# 2_ADSTM32-MCU.net
KiCad netlist of a schematic drawn in Altium Designer
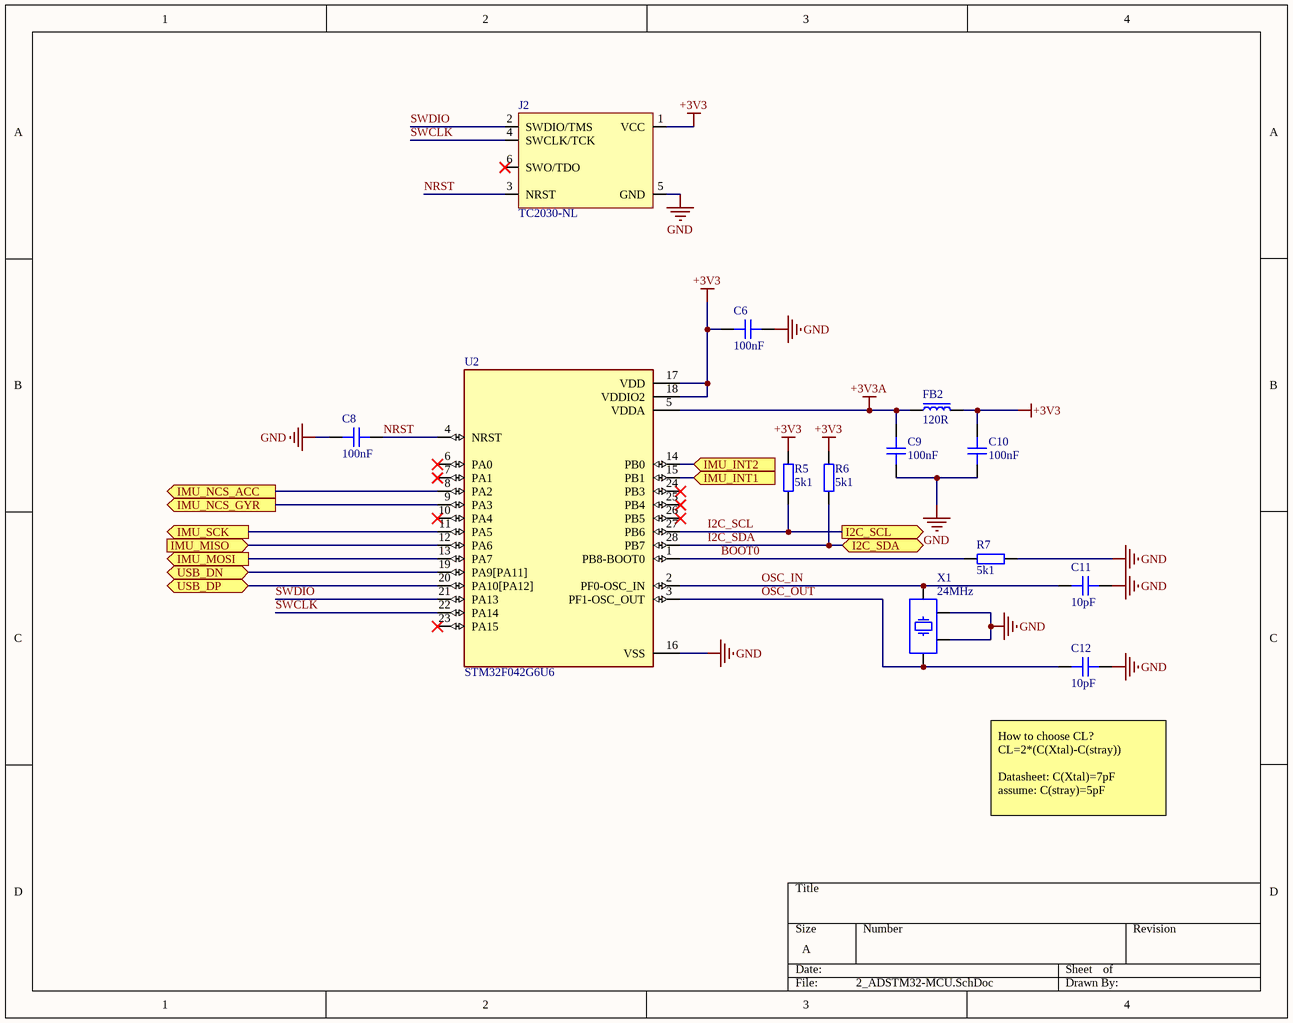
[diagram p0: 2_ADSTM32-MCU.SchDoc]

(export (version "E")
  (design (tool "Eeschema 10.0.6"))
  (components
    (comp (ref "C6")
      (value "100nF")
      (footprint "CAP_0603")
      (description "Capacitor SMD 0603")
      (libsource (lib "Schematic-Lib-PhilsLab") (part "CAP_0603"))
    )
    (comp (ref "C8")
      (value "100nF")
      (footprint "CAP_0603")
      (description "Capacitor SMD 0603")
      (libsource (lib "Schematic-Lib-PhilsLab") (part "CAP_0603"))
    )
    (comp (ref "C9")
      (value "100nF")
      (footprint "CAP_0603")
      (description "Capacitor SMD 0603")
      (libsource (lib "Schematic-Lib-PhilsLab") (part "CAP_0603"))
    )
    (comp (ref "C10")
      (value "100nF")
      (footprint "CAP_0603")
      (description "Capacitor SMD 0603")
      (libsource (lib "Schematic-Lib-PhilsLab") (part "CAP_0603"))
    )
    (comp (ref "C11")
      (value "10pF")
      (footprint "CAP_0603")
      (description "Capacitor SMD 0603")
      (libsource (lib "Schematic-Lib-PhilsLab") (part "CAP_0603"))
    )
    (comp (ref "C12")
      (value "10pF")
      (footprint "CAP_0603")
      (description "Capacitor SMD 0603")
      (libsource (lib "Schematic-Lib-PhilsLab") (part "CAP_0603"))
    )
    (comp (ref "FB2")
      (value "120R")
      (footprint "FB_0603")
      (description "Ferrite Bead SMD 0603")
      (libsource (lib "Schematic-Lib-PhilsLab") (part "FB_0603"))
    )
    (comp (ref "J2")
      (value "TC2030-NL")
      (footprint "TC2030-NL-FP")
      (description "Tag-Connect No-Solder SWD Debug Connector (No Legs) DO NOT PLACE")
      (fields
        (field (name "MANUFACTURER") "Tag-Connect")
        (field (name "MANUFACTURER PART NUMBER") "TC2030-NL-FP")
      )
      (libsource (lib "Schematic-Lib-PhilsLab") (part "TC2030-NL"))
    )
    (comp (ref "R5")
      (value "5k1")
      (footprint "RES_0603")
      (description "Resistor SMD 0603")
      (libsource (lib "Schematic-Lib-PhilsLab") (part "RES_0603"))
    )
    (comp (ref "R6")
      (value "5k1")
      (footprint "RES_0603")
      (description "Resistor SMD 0603")
      (libsource (lib "Schematic-Lib-PhilsLab") (part "RES_0603"))
    )
    (comp (ref "R7")
      (value "5k1")
      (footprint "RES_0603")
      (description "Resistor SMD 0603")
      (libsource (lib "Schematic-Lib-PhilsLab") (part "RES_0603"))
    )
    (comp (ref "U2")
      (value "STM32F042G6U6")
      (footprint "STM32F042G6U6")
      (fields (field (name "MANUFACTURER") "STMicroelectronics"))
      (libsource (lib "Schlib1") (part "STM32F042G6U6"))
    )
    (comp (ref "X1")
      (value "24MHz")
      (footprint "XTAL_3225")
      (description "Crystal SMD 24MHz 10PPM 7pF 3225")
      (fields
        (field (name "MANUFACTURER") "Epson")
        (field (name "MANUFACTURER PART NUMBER") "TSX-3225 24.0000MF15X-AC")
      )
      (libsource (lib "Schematic-Lib-PhilsLab") (part "TSX-3225_24.0000MF15X-AC"))
    )
  )
  (nets
    (net (code "1") (name "+3V3") (class "Default")
      (node (ref "C10") (pin "2") (pinfunction "2_2") (pintype "passive"))
      (node (ref "C6") (pin "2") (pinfunction "2_2") (pintype "passive"))
      (node (ref "FB2") (pin "2") (pinfunction "2_2") (pintype "passive"))
      (node (ref "J2") (pin "1") (pinfunction "VCC_1") (pintype "passive"))
      (node (ref "R5") (pin "2") (pinfunction "2_2") (pintype "passive"))
      (node (ref "R6") (pin "2") (pinfunction "2_2") (pintype "passive"))
      (node (ref "U2") (pin "17") (pinfunction "VDD_17") (pintype "power_in"))
      (node (ref "U2") (pin "18") (pinfunction "VDDIO2_18") (pintype "power_in"))
    )
    (net (code "2") (name "+3V3A") (class "Default")
      (node (ref "C9") (pin "2") (pinfunction "2_2") (pintype "passive"))
      (node (ref "FB2") (pin "1") (pinfunction "1_1") (pintype "passive"))
      (node (ref "U2") (pin "5") (pinfunction "VDDA_5") (pintype "power_in"))
    )
    (net (code "3") (name "/BOOT0") (class "Default")
      (node (ref "R7") (pin "2") (pinfunction "2_2") (pintype "passive"))
      (node (ref "U2") (pin "1") (pinfunction "PB8-BOOT0_1") (pintype "bidirectional"))
    )
    (net (code "4") (name "/I2C_SCL") (class "Default")
      (node (ref "R5") (pin "1") (pinfunction "1_1") (pintype "passive"))
      (node (ref "U2") (pin "27") (pinfunction "PB6_27") (pintype "bidirectional"))
    )
    (net (code "5") (name "/I2C_SDA") (class "Default")
      (node (ref "R6") (pin "1") (pinfunction "1_1") (pintype "passive"))
      (node (ref "U2") (pin "28") (pinfunction "PB7_28") (pintype "bidirectional"))
    )
    (net (code "6") (name "/IMU_INT1") (class "Default")
      (node (ref "U2") (pin "15") (pinfunction "PB1_15") (pintype "bidirectional"))
    )
    (net (code "7") (name "/IMU_INT2") (class "Default")
      (node (ref "U2") (pin "14") (pinfunction "PB0_14") (pintype "bidirectional"))
    )
    (net (code "8") (name "/IMU_MISO") (class "Default")
      (node (ref "U2") (pin "12") (pinfunction "PA6_12") (pintype "bidirectional"))
    )
    (net (code "9") (name "/IMU_MOSI") (class "Default")
      (node (ref "U2") (pin "13") (pinfunction "PA7_13") (pintype "bidirectional"))
    )
    (net (code "10") (name "/IMU_NCS_ACC") (class "Default")
      (node (ref "U2") (pin "8") (pinfunction "PA2_8") (pintype "bidirectional"))
    )
    (net (code "11") (name "/IMU_NCS_GYR") (class "Default")
      (node (ref "U2") (pin "9") (pinfunction "PA3_9") (pintype "bidirectional"))
    )
    (net (code "12") (name "/IMU_SCK") (class "Default")
      (node (ref "U2") (pin "11") (pinfunction "PA5_11") (pintype "bidirectional"))
    )
    (net (code "13") (name "/NRST") (class "Default")
      (node (ref "C8") (pin "1") (pinfunction "1_1") (pintype "passive"))
      (node (ref "J2") (pin "3") (pinfunction "NRST_3") (pintype "passive"))
      (node (ref "U2") (pin "4") (pinfunction "NRST_4") (pintype "bidirectional"))
    )
    (net (code "14") (name "/OSC_IN") (class "Default")
      (node (ref "C11") (pin "2") (pinfunction "2_2") (pintype "passive"))
      (node (ref "U2") (pin "2") (pinfunction "PF0-OSC_IN_2") (pintype "bidirectional"))
      (node (ref "X1") (pin "3") (pinfunction "3_3") (pintype "passive"))
    )
    (net (code "15") (name "/OSC_OUT") (class "Default")
      (node (ref "C12") (pin "2") (pinfunction "2_2") (pintype "passive"))
      (node (ref "U2") (pin "3") (pinfunction "PF1-OSC_OUT_3") (pintype "bidirectional"))
      (node (ref "X1") (pin "1") (pinfunction "1_1") (pintype "passive"))
    )
    (net (code "16") (name "/SWCLK") (class "Default")
      (node (ref "J2") (pin "4") (pinfunction "SWCLK/TCK_4") (pintype "passive"))
      (node (ref "U2") (pin "22") (pinfunction "PA14_22") (pintype "bidirectional"))
    )
    (net (code "17") (name "/SWDIO") (class "Default")
      (node (ref "J2") (pin "2") (pinfunction "SWDIO/TMS_2") (pintype "passive"))
      (node (ref "U2") (pin "21") (pinfunction "PA13_21") (pintype "bidirectional"))
    )
    (net (code "18") (name "/USB_DN") (class "Default")
      (node (ref "U2") (pin "19") (pinfunction "PA9[PA11]_19") (pintype "bidirectional"))
    )
    (net (code "19") (name "/USB_DP") (class "Default")
      (node (ref "U2") (pin "20") (pinfunction "PA10[PA12]_20") (pintype "bidirectional"))
    )
    (net (code "20") (name "GND") (class "Default")
      (node (ref "C10") (pin "1") (pinfunction "1_1") (pintype "passive"))
      (node (ref "C11") (pin "1") (pinfunction "1_1") (pintype "passive"))
      (node (ref "C12") (pin "1") (pinfunction "1_1") (pintype "passive"))
      (node (ref "C6") (pin "1") (pinfunction "1_1") (pintype "passive"))
      (node (ref "C8") (pin "2") (pinfunction "2_2") (pintype "passive"))
      (node (ref "C9") (pin "1") (pinfunction "1_1") (pintype "passive"))
      (node (ref "J2") (pin "5") (pinfunction "GND_5") (pintype "passive"))
      (node (ref "R7") (pin "1") (pinfunction "1_1") (pintype "passive"))
      (node (ref "U2") (pin "16") (pinfunction "VSS_16") (pintype "power_in"))
      (node (ref "X1") (pin "2") (pinfunction "2_2") (pintype "passive"))
      (node (ref "X1") (pin "4") (pinfunction "4_4") (pintype "passive"))
    )
    (net (code "21") (name "unconnected-(J2-SWO{slash}TDO-Pad6)") (class "Default")
      (node (ref "J2") (pin "6") (pinfunction "SWO/TDO_6") (pintype "passive+no_connect"))
    )
    (net (code "22") (name "unconnected-(U2-PA0-Pad6)") (class "Default")
      (node (ref "U2") (pin "6") (pinfunction "PA0_6") (pintype "bidirectional+no_connect"))
    )
    (net (code "23") (name "unconnected-(U2-PA1-Pad7)") (class "Default")
      (node (ref "U2") (pin "7") (pinfunction "PA1_7") (pintype "bidirectional+no_connect"))
    )
    (net (code "24") (name "unconnected-(U2-PA4-Pad10)") (class "Default")
      (node (ref "U2") (pin "10") (pinfunction "PA4_10") (pintype "bidirectional+no_connect"))
    )
    (net (code "25") (name "unconnected-(U2-PA15-Pad23)") (class "Default")
      (node (ref "U2") (pin "23") (pinfunction "PA15_23") (pintype "bidirectional+no_connect"))
    )
    (net (code "26") (name "unconnected-(U2-PB3-Pad24)") (class "Default")
      (node (ref "U2") (pin "24") (pinfunction "PB3_24") (pintype "bidirectional+no_connect"))
    )
    (net (code "27") (name "unconnected-(U2-PB4-Pad25)") (class "Default")
      (node (ref "U2") (pin "25") (pinfunction "PB4_25") (pintype "bidirectional+no_connect"))
    )
    (net (code "28") (name "unconnected-(U2-PB5-Pad26)") (class "Default")
      (node (ref "U2") (pin "26") (pinfunction "PB5_26") (pintype "bidirectional+no_connect"))
    )
  )
)
